# 5V0_EXT_SUPPLY.net
KiCad netlist of a schematic drawn in Altium Designer
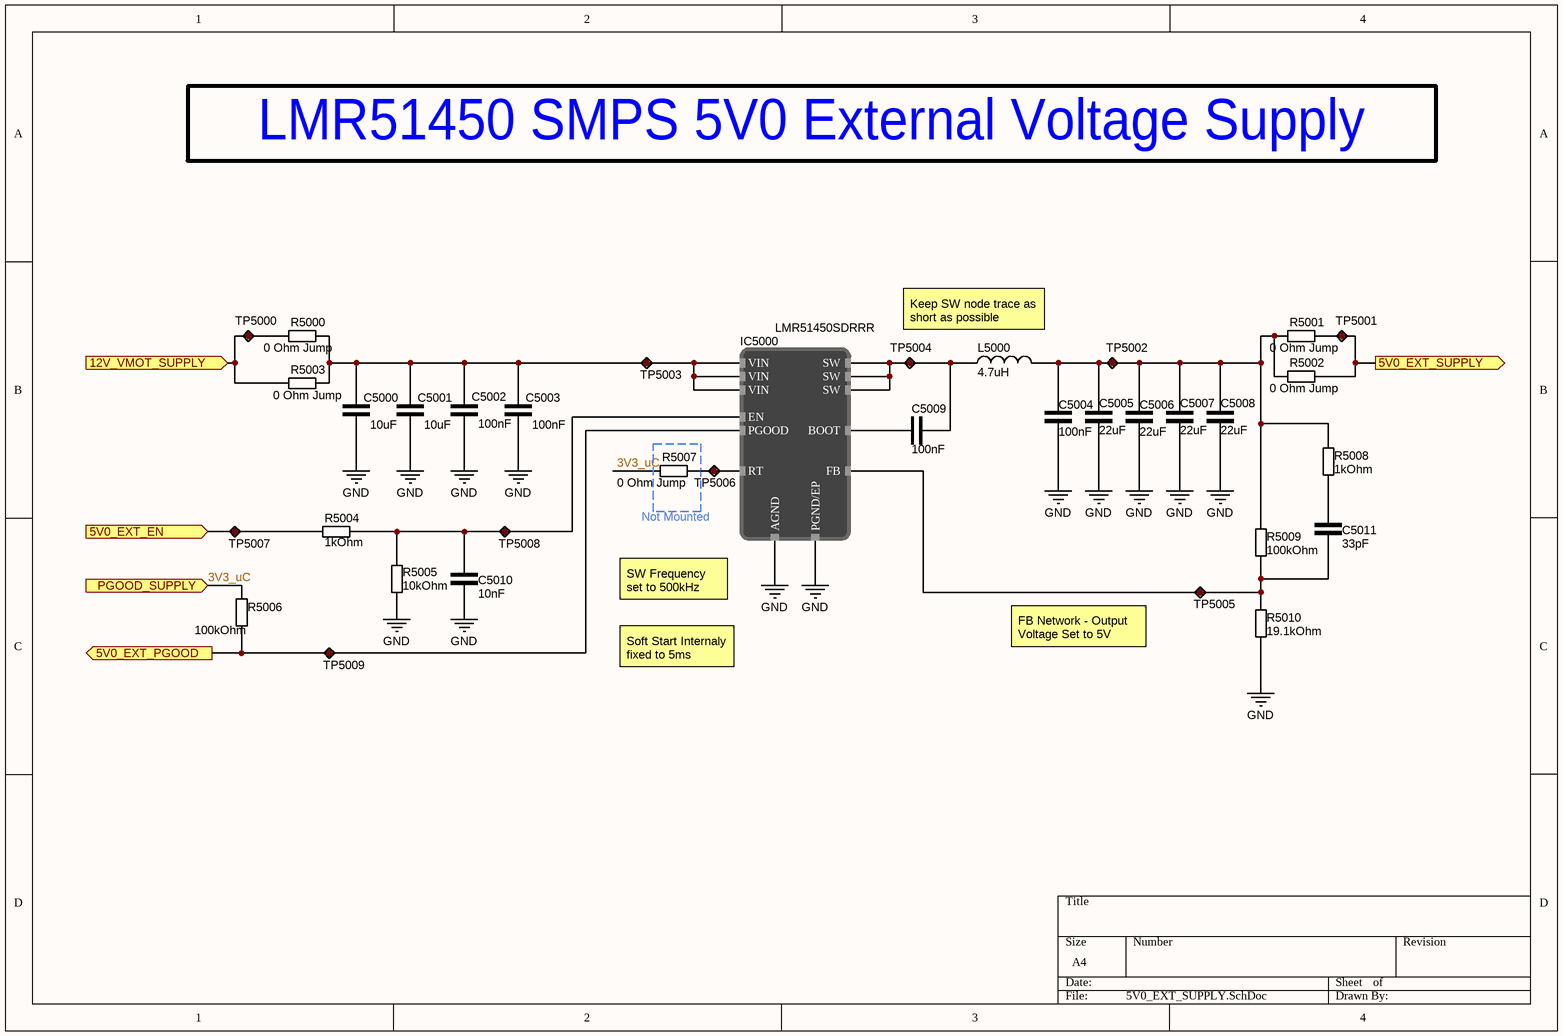
[diagram p0: 5V0_EXT_SUPPLY.SchDoc]

(export (version "E")
  (design (tool "Eeschema 10.0.6"))
  (components
    (comp (ref "C5000")
      (value "10uF")
      (footprint "CAP_0805")
      (description "10 µF ±10% 25V Ceramic Capacitor X5R 0805 (2012 Metric)")
      (fields (field (name "DIGIKEY PART NUMBER") "445-5984-1-ND"))
      (libsource (lib "CapacitorsIntegrated") (part "C000002"))
    )
    (comp (ref "C5001")
      (value "10uF")
      (footprint "CAP_0805")
      (description "10 µF ±10% 25V Ceramic Capacitor X5R 0805 (2012 Metric)")
      (fields (field (name "DIGIKEY PART NUMBER") "445-5984-1-ND"))
      (libsource (lib "CapacitorsIntegrated") (part "C000002"))
    )
    (comp (ref "C5002")
      (value "100nF")
      (footprint "CAP_0603")
      (description "0.1 µF ±10% 25V Ceramic Capacitor X7R 0603 (1608 Metric)")
      (fields (field (name "DIGIKEY PART NUMBER") "478-KAM15AR71E104KTCT-ND"))
      (libsource (lib "CapacitorsIntegrated") (part "C000007"))
    )
    (comp (ref "C5003")
      (value "100nF")
      (footprint "CAP_0603")
      (description "0.1 µF ±10% 25V Ceramic Capacitor X7R 0603 (1608 Metric)")
      (fields (field (name "DIGIKEY PART NUMBER") "478-KAM15AR71E104KTCT-ND"))
      (libsource (lib "") (part "C000007_1"))
    )
    (comp (ref "C5004")
      (value "100nF")
      (footprint "CAP_0603")
      (description "0.1 µF ±10% 25V Ceramic Capacitor X7R 0603 (1608 Metric)")
      (fields (field (name "DIGIKEY PART NUMBER") "478-KAM15AR71E104KTCT-ND"))
      (libsource (lib "") (part "C000007_1"))
    )
    (comp (ref "C5005")
      (value "22uF")
      (footprint "CAP_0805")
      (description "22 µF ±20% 25V Ceramic Capacitor X5R 0805 (2012 Metric)")
      (fields (field (name "DIGIKEY PART NUMBER") "445-9112-1-ND"))
      (libsource (lib "CapacitorsIntegrated") (part "C000001"))
    )
    (comp (ref "C5006")
      (value "22uF")
      (footprint "CAP_0805")
      (description "22 µF ±20% 25V Ceramic Capacitor X5R 0805 (2012 Metric)")
      (fields (field (name "DIGIKEY PART NUMBER") "445-9112-1-ND"))
      (libsource (lib "") (part "C000001_1"))
    )
    (comp (ref "C5007")
      (value "22uF")
      (footprint "CAP_0805")
      (description "22 µF ±20% 25V Ceramic Capacitor X5R 0805 (2012 Metric)")
      (fields (field (name "DIGIKEY PART NUMBER") "445-9112-1-ND"))
      (libsource (lib "CapacitorsIntegrated") (part "C000001"))
    )
    (comp (ref "C5008")
      (value "22uF")
      (footprint "CAP_0805")
      (description "22 µF ±20% 25V Ceramic Capacitor X5R 0805 (2012 Metric)")
      (fields (field (name "DIGIKEY PART NUMBER") "445-9112-1-ND"))
      (libsource (lib "CapacitorsIntegrated") (part "C000001"))
    )
    (comp (ref "C5009")
      (value "100nF")
      (footprint "CAP_0603")
      (description "0.1 µF ±10% 25V Ceramic Capacitor X7R 0603 (1608 Metric)")
      (fields (field (name "DIGIKEY PART NUMBER") "478-KAM15AR71E104KTCT-ND"))
      (libsource (lib "") (part "C000007_2"))
    )
    (comp (ref "C5010")
      (value "10nF")
      (footprint "CAP_0603")
      (description "10000 pF ±20% 25V Ceramic Capacitor X7R 0603 (1608 Metric)")
      (fields (field (name "DIGIKEY PART NUMBER") "478-KGM15AR71E103MTCT-ND"))
      (libsource (lib "CapacitorsIntegrated") (part "C000005"))
    )
    (comp (ref "C5011")
      (value "33pF")
      (footprint "CAP_0603")
      (description "33 pF ±5% 25V Ceramic Capacitor C0G, NP0 0603 (1608 Metric)")
      (fields (field (name "DIGIKEY PART NUMBER") "311-3954-1-ND"))
      (libsource (lib "CapacitorsIntegrated") (part "C000029"))
    )
    (comp (ref "IC5000")
      (value "LMR51450SDRRR")
      (footprint "SON50P300X80_HS-13N")
      (description "Buck Switching Regulator IC Positive Adjustable 0.8V 1 Output 5A 12-WFDFN Exposed Pad")
      (fields
        (field (name "DIGIKEY PART NUMBER") "296-LMR51450SDRRRCT-ND")
        (field (name "MOUSER PART NUMBER") "595-LMR51450SDRRR")
      )
      (libsource (lib "IntegratedCircuits") (part "LMR51450SDRRR"))
    )
    (comp (ref "L5000")
      (value "4.7uH")
      (footprint "INDP6965X30N")
      (description "FIXED IND 4.7UH 5.5A 40 MOHM SMD")
      (fields (field (name "DIGIKEY PART NUMBER") "541-1010-1-ND"))
      (libsource (lib "InductorIntegrated") (part "L000011"))
    )
    (comp (ref "R5000")
      (value "0 Ohm Jump")
      (footprint "RES_0805")
      (description "0 Ohms Jumper Chip Resistor 0805 (2012 Metric) Automotive AEC-Q200 Thick Film")
      (fields (field (name "DIGIKEY PART NUMBER") "P0.0ACT-ND"))
      (libsource (lib "ResistorsIntegrated") (part "R000011"))
    )
    (comp (ref "R5001")
      (value "0 Ohm Jump")
      (footprint "RES_1206")
      (description "0 Ohms Jumper Chip Resistor 1206 (3216 Metric) Automotive AEC-Q200 Thick Film")
      (fields (field (name "DIGIKEY PART NUMBER") "RMCF1206ZT0R00CT-ND"))
      (libsource (lib "ResistorsIntegrated") (part "R000012"))
    )
    (comp (ref "R5002")
      (value "0 Ohm Jump")
      (footprint "RES_1206")
      (description "0 Ohms Jumper Chip Resistor 1206 (3216 Metric) Automotive AEC-Q200 Thick Film")
      (fields (field (name "DIGIKEY PART NUMBER") "RMCF1206ZT0R00CT-ND"))
      (libsource (lib "ResistorsIntegrated") (part "R000012"))
    )
    (comp (ref "R5003")
      (value "0 Ohm Jump")
      (footprint "RES_0805")
      (description "0 Ohms Jumper Chip Resistor 0805 (2012 Metric) Automotive AEC-Q200 Thick Film")
      (fields (field (name "DIGIKEY PART NUMBER") "P0.0ACT-ND"))
      (libsource (lib "ResistorsIntegrated") (part "R000011"))
    )
    (comp (ref "R5004")
      (value "1kOhm")
      (footprint "RES_0603")
      (description "1 kOhms ±1% 0.125W, 1/8W Chip Resistor 0603 (1608 Metric) Anti-Sulfur Thin Film")
      (fields (field (name "DIGIKEY PART NUMBER") "MCT0603-1.00K-CFCT-ND"))
      (libsource (lib "ResistorsIntegrated") (part "R000004"))
    )
    (comp (ref "R5005")
      (value "10kOhm")
      (footprint "RES_0603")
      (description "10 kOhms ±1% 0.125W, 1/8W Chip Resistor 0603 (1608 Metric) Anti-Sulfur Thin Film")
      (fields (field (name "DIGIKEY PART NUMBER") "MCT0603-10.0K-CFCT-ND"))
      (libsource (lib "ResistorsIntegrated") (part "R000001"))
    )
    (comp (ref "R5006")
      (value "100kOhm")
      (footprint "RES_0603")
      (description "100 kOhms ±1% 0.1W, 1/10W Chip Resistor 0603 (1608 Metric) Automotive AEC-Q200 Thick Film")
      (fields (field (name "DIGIKEY PART NUMBER") "RMCF0603FG100KCT-ND"))
      (libsource (lib "ResistorsIntegrated") (part "R000006"))
    )
    (comp (ref "R5007")
      (value "0 Ohm Jump")
      (footprint "RES_0603")
      (description "0 Ohms Jumper Chip Resistor 0603 (1608 Metric) Automotive AEC-Q200 Thick Film")
      (fields (field (name "DIGIKEY PART NUMBER") "RMCF0603ZT0R00CT-ND"))
      (libsource (lib "ResistorsIntegrated") (part "R000007"))
    )
    (comp (ref "R5008")
      (value "1kOhm")
      (footprint "RES_0603")
      (description "1 kOhms ±1% 0.125W, 1/8W Chip Resistor 0603 (1608 Metric) Anti-Sulfur Thin Film")
      (fields (field (name "DIGIKEY PART NUMBER") "MCT0603-1.00K-CFCT-ND"))
      (libsource (lib "") (part "R000004_1"))
    )
    (comp (ref "R5009")
      (value "100kOhm")
      (footprint "RES_0603")
      (description "100 kOhms ±1% 0.1W, 1/10W Chip Resistor 0603 (1608 Metric) Automotive AEC-Q200 Thick Film")
      (fields (field (name "DIGIKEY PART NUMBER") "RMCF0603FG100KCT-ND"))
      (libsource (lib "ResistorsIntegrated") (part "R000006"))
    )
    (comp (ref "R5010")
      (value "19.1kOhm")
      (footprint "RES_0603")
      (description "19.1 kOhms ±1% 0.1W, 1/10W Chip Resistor 0603 (1608 Metric) Moisture Resistant Thick Film")
      (fields (field (name "DIGIKEY PART NUMBER") "311-19.1KHRCT-ND"))
      (libsource (lib "ResistorsIntegrated") (part "R000020"))
    )
    (comp (ref "TP5000")
      (value "Test point")
      (footprint "TestPoint")
      (description "Test point 1mm")
      (libsource (lib "IntegratedCircuits") (part "TP002"))
    )
    (comp (ref "TP5001")
      (value "Test point")
      (footprint "TestPoint")
      (description "Test point 1mm")
      (libsource (lib "IntegratedCircuits") (part "TP002"))
    )
    (comp (ref "TP5002")
      (value "Test point")
      (footprint "TestPoint")
      (description "Test point 1mm")
      (libsource (lib "IntegratedCircuits") (part "TP002"))
    )
    (comp (ref "TP5003")
      (value "Test point")
      (footprint "TestPoint")
      (description "Test point 1mm")
      (libsource (lib "IntegratedCircuits") (part "TP002"))
    )
    (comp (ref "TP5004")
      (value "Test point")
      (footprint "TestPoint")
      (description "Test point 1mm")
      (libsource (lib "IntegratedCircuits") (part "TP002"))
    )
    (comp (ref "TP5005")
      (value "Test point")
      (footprint "TestPoint")
      (description "Test point 1mm")
      (libsource (lib "IntegratedCircuits") (part "TP002"))
    )
    (comp (ref "TP5006")
      (value "Test point")
      (footprint "TestPoint")
      (description "Test point 1mm")
      (libsource (lib "IntegratedCircuits") (part "TP002"))
    )
    (comp (ref "TP5007")
      (value "Test point")
      (footprint "TestPoint")
      (description "Test point 1mm")
      (libsource (lib "IntegratedCircuits") (part "TP002"))
    )
    (comp (ref "TP5008")
      (value "Test point")
      (footprint "TestPoint")
      (description "Test point 1mm")
      (libsource (lib "IntegratedCircuits") (part "TP002"))
    )
    (comp (ref "TP5009")
      (value "Test point")
      (footprint "TestPoint")
      (description "Test point 1mm")
      (libsource (lib "IntegratedCircuits") (part "TP002"))
    )
  )
  (nets
    (net (code "1") (name "/3V3_uC") (class "Default")
      (node (ref "R5006") (pin "2") (pinfunction "2_2") (pintype "passive"))
      (node (ref "R5007") (pin "1") (pinfunction "1_1") (pintype "passive"))
    )
    (net (code "2") (name "/5V0_EXT_EN") (class "Default")
      (node (ref "R5004") (pin "1") (pinfunction "1_1") (pintype "passive"))
      (node (ref "TP5007") (pin "1") (pinfunction "1_1") (pintype "passive"))
    )
    (net (code "3") (name "/5V0_EXT_PGOOD") (class "Default")
      (node (ref "IC5000") (pin "5") (pinfunction "PGOOD_5") (pintype "passive"))
      (node (ref "R5006") (pin "1") (pinfunction "1_1") (pintype "passive"))
      (node (ref "TP5009") (pin "1") (pinfunction "1_1") (pintype "passive"))
    )
    (net (code "4") (name "/5V0_EXT_SUPPLY") (class "Default")
      (node (ref "R5001") (pin "2") (pinfunction "2_2") (pintype "passive"))
      (node (ref "R5002") (pin "2") (pinfunction "2_2") (pintype "passive"))
      (node (ref "TP5001") (pin "1") (pinfunction "1_1") (pintype "passive"))
    )
    (net (code "5") (name "/12V_VMOT_SUPPLY") (class "Default")
      (node (ref "R5000") (pin "1") (pinfunction "1_1") (pintype "passive"))
      (node (ref "R5003") (pin "1") (pinfunction "1_1") (pintype "passive"))
      (node (ref "TP5000") (pin "1") (pinfunction "1_1") (pintype "passive"))
    )
    (net (code "6") (name "GND") (class "Default")
      (node (ref "C5000") (pin "1") (pinfunction "1_1") (pintype "passive"))
      (node (ref "C5001") (pin "1") (pinfunction "1_1") (pintype "passive"))
      (node (ref "C5002") (pin "2") (pinfunction "2_2") (pintype "passive"))
      (node (ref "C5003") (pin "1") (pinfunction "1_1") (pintype "passive"))
      (node (ref "C5004") (pin "1") (pinfunction "1_1") (pintype "passive"))
      (node (ref "C5005") (pin "1") (pinfunction "1_1") (pintype "passive"))
      (node (ref "C5006") (pin "2") (pinfunction "2_2") (pintype "passive"))
      (node (ref "C5007") (pin "1") (pinfunction "1_1") (pintype "passive"))
      (node (ref "C5008") (pin "1") (pinfunction "1_1") (pintype "passive"))
      (node (ref "C5010") (pin "1") (pinfunction "1_1") (pintype "passive"))
      (node (ref "IC5000") (pin "13") (pinfunction "PGND/EP_13") (pintype "passive"))
      (node (ref "IC5000") (pin "8") (pinfunction "AGND_8") (pintype "passive"))
      (node (ref "R5005") (pin "1") (pinfunction "1_1") (pintype "passive"))
      (node (ref "R5010") (pin "1") (pinfunction "1_1") (pintype "passive"))
    )
    (net (code "7") (name "Net-(C5000-Pad2)") (class "Default")
      (node (ref "C5000") (pin "2") (pinfunction "2_2") (pintype "passive"))
      (node (ref "C5001") (pin "2") (pinfunction "2_2") (pintype "passive"))
      (node (ref "C5002") (pin "1") (pinfunction "1_1") (pintype "passive"))
      (node (ref "C5003") (pin "2") (pinfunction "2_2") (pintype "passive"))
      (node (ref "IC5000") (pin "10") (pinfunction "VIN_10") (pintype "passive"))
      (node (ref "IC5000") (pin "11") (pinfunction "VIN_11") (pintype "passive"))
      (node (ref "IC5000") (pin "12") (pinfunction "VIN_12") (pintype "passive"))
      (node (ref "R5000") (pin "2") (pinfunction "2_2") (pintype "passive"))
      (node (ref "R5003") (pin "2") (pinfunction "2_2") (pintype "passive"))
      (node (ref "TP5003") (pin "1") (pinfunction "1_1") (pintype "passive"))
    )
    (net (code "8") (name "Net-(C5004-Pad2)") (class "Default")
      (node (ref "C5004") (pin "2") (pinfunction "2_2") (pintype "passive"))
      (node (ref "C5005") (pin "2") (pinfunction "2_2") (pintype "passive"))
      (node (ref "C5006") (pin "1") (pinfunction "1_1") (pintype "passive"))
      (node (ref "C5007") (pin "2") (pinfunction "2_2") (pintype "passive"))
      (node (ref "C5008") (pin "2") (pinfunction "2_2") (pintype "passive"))
      (node (ref "L5000") (pin "2") (pinfunction "2_2") (pintype "passive"))
      (node (ref "R5001") (pin "1") (pinfunction "1_1") (pintype "passive"))
      (node (ref "R5002") (pin "1") (pinfunction "1_1") (pintype "passive"))
      (node (ref "R5008") (pin "2") (pinfunction "2_2") (pintype "passive"))
      (node (ref "R5009") (pin "2") (pinfunction "2_2") (pintype "passive"))
      (node (ref "TP5002") (pin "1") (pinfunction "1_1") (pintype "passive"))
    )
    (net (code "9") (name "Net-(C5009-Pad2)") (class "Default")
      (node (ref "C5009") (pin "2") (pinfunction "2_2") (pintype "passive"))
      (node (ref "IC5000") (pin "1") (pinfunction "SW_1") (pintype "passive"))
      (node (ref "IC5000") (pin "2") (pinfunction "SW_2") (pintype "passive"))
      (node (ref "IC5000") (pin "3") (pinfunction "SW_3") (pintype "passive"))
      (node (ref "L5000") (pin "1") (pinfunction "1_1") (pintype "passive"))
      (node (ref "TP5004") (pin "1") (pinfunction "1_1") (pintype "passive"))
    )
    (net (code "10") (name "Net-(C5011-Pad2)") (class "Default")
      (node (ref "C5011") (pin "2") (pinfunction "2_2") (pintype "passive"))
      (node (ref "R5008") (pin "1") (pinfunction "1_1") (pintype "passive"))
    )
    (net (code "11") (name "Net-(IC5000-BOOT)") (class "Default")
      (node (ref "C5009") (pin "1") (pinfunction "1_1") (pintype "passive"))
      (node (ref "IC5000") (pin "4") (pinfunction "BOOT_4") (pintype "passive"))
    )
    (net (code "12") (name "Net-(IC5000-EN)") (class "Default")
      (node (ref "C5010") (pin "2") (pinfunction "2_2") (pintype "passive"))
      (node (ref "IC5000") (pin "9") (pinfunction "EN_9") (pintype "passive"))
      (node (ref "R5004") (pin "2") (pinfunction "2_2") (pintype "passive"))
      (node (ref "R5005") (pin "2") (pinfunction "2_2") (pintype "passive"))
      (node (ref "TP5008") (pin "1") (pinfunction "1_1") (pintype "passive"))
    )
    (net (code "13") (name "Net-(IC5000-FB)") (class "Default")
      (node (ref "C5011") (pin "1") (pinfunction "1_1") (pintype "passive"))
      (node (ref "IC5000") (pin "7") (pinfunction "FB_7") (pintype "passive"))
      (node (ref "R5009") (pin "1") (pinfunction "1_1") (pintype "passive"))
      (node (ref "R5010") (pin "2") (pinfunction "2_2") (pintype "passive"))
      (node (ref "TP5005") (pin "1") (pinfunction "1_1") (pintype "passive"))
    )
    (net (code "14") (name "Net-(IC5000-RT)") (class "Default")
      (node (ref "IC5000") (pin "6") (pinfunction "RT_6") (pintype "passive"))
      (node (ref "R5007") (pin "2") (pinfunction "2_2") (pintype "passive"))
      (node (ref "TP5006") (pin "1") (pinfunction "1_1") (pintype "passive"))
    )
  )
)
